# Motors.net
KiCad netlist of a schematic drawn in Altium Designer
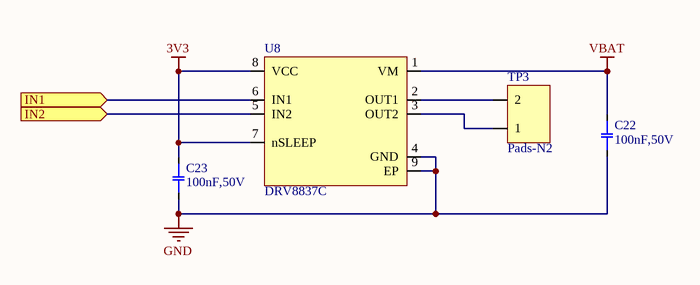
[diagram p0: Motors.SchDoc]

(export (version "E")
  (design (tool "Eeschema 10.0.6"))
  (components
    (comp (ref "C22")
      (value "100nF,50V")
      (footprint "CAPC1608X09N_0603")
      (description "CAP CER 0.1UF 50V 10% X7R 0603")
      (fields (field (name "MANUFACTURER") "Kemet") (field (name "TOLERANCE") "10%"))
      (libsource (lib "library") (part "CAP-NP_1"))
    )
    (comp (ref "C23")
      (value "100nF,50V")
      (footprint "CAPC1608X09N_0603")
      (description "CAP CER 0.1UF 50V 10% X7R 0603")
      (fields (field (name "MANUFACTURER") "Kemet") (field (name "TOLERANCE") "10%"))
      (libsource (lib "library") (part "CAP-NP_1"))
    )
    (comp (ref "TP3") (value "Pads-N2") (footprint "PADS-N2") (libsource (lib "Common") (part "Pads-N2")))
    (comp (ref "U8")
      (value "DRV8837C")
      (footprint "DFN50P200X200X80-8N")
      (description "IC HALF-BRIDGE DRVR PWM 8WSON")
      (fields
        (field (name "MANUFACTURER") "Texas Instruments")
        (field (name "MANUFACTURER PART NUMBER") "DRV8837CDSGR")
      )
      (libsource (lib "library") (part "DRV8837C"))
    )
  )
  (nets
    (net (code "1") (name "/IN1") (class "Default")
      (node (ref "U8") (pin "6") (pinfunction "IN1_6") (pintype "passive"))
    )
    (net (code "2") (name "/IN2") (class "Default")
      (node (ref "U8") (pin "5") (pinfunction "IN2_5") (pintype "passive"))
    )
    (net (code "3") (name "3V3") (class "Default")
      (node (ref "C23") (pin "2") (pinfunction "2_2") (pintype "passive"))
      (node (ref "U8") (pin "7") (pinfunction "nSLEEP_7") (pintype "passive"))
      (node (ref "U8") (pin "8") (pinfunction "VCC_8") (pintype "passive"))
    )
    (net (code "4") (name "GND") (class "Default")
      (node (ref "C22") (pin "1") (pinfunction "1_1") (pintype "passive"))
      (node (ref "C23") (pin "1") (pinfunction "1_1") (pintype "passive"))
      (node (ref "U8") (pin "4") (pinfunction "GND_4") (pintype "passive"))
      (node (ref "U8") (pin "9") (pinfunction "EP_9") (pintype "passive"))
    )
    (net (code "5") (name "Net-(U8-OUT1)") (class "Default")
      (node (ref "TP3") (pin "2") (pinfunction "2_2") (pintype "passive"))
      (node (ref "U8") (pin "2") (pinfunction "OUT1_2") (pintype "passive"))
    )
    (net (code "6") (name "Net-(U8-OUT2)") (class "Default")
      (node (ref "TP3") (pin "1") (pinfunction "1_1") (pintype "passive"))
      (node (ref "U8") (pin "3") (pinfunction "OUT2_3") (pintype "passive"))
    )
    (net (code "7") (name "VBAT") (class "Default")
      (node (ref "C22") (pin "2") (pinfunction "2_2") (pintype "passive"))
      (node (ref "U8") (pin "1") (pinfunction "VM_1") (pintype "passive"))
    )
  )
)
